# PATHOS_SOM_UART.net
KiCad netlist of a schematic drawn in Altium Designer
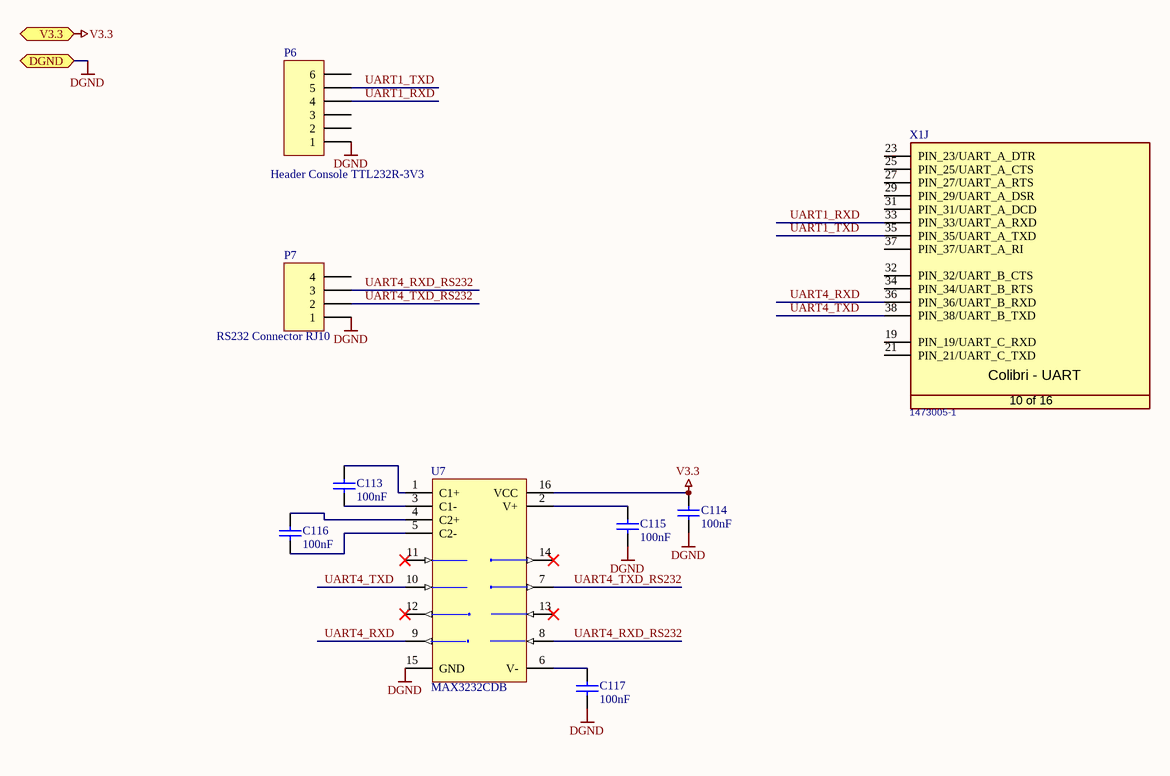
[diagram p0: PATHOS_SOM_UART.SchDoc]

(export (version "E")
  (design (tool "Eeschema 10.0.6"))
  (components
    (comp (ref "C113")
      (value "100nF")
      (footprint "0603_3D")
      (description "Capacitor")
      (fields (field (name "#PUBLISHER") "Dr. A. Heinzelmann"))
      (libsource (lib "EFS_Sensorboard") (part "C"))
    )
    (comp (ref "C114")
      (value "100nF")
      (footprint "0603_3D")
      (description "Capacitor")
      (fields (field (name "#PUBLISHER") "Dr. A. Heinzelmann"))
      (libsource (lib "EFS_Sensorboard") (part "C"))
    )
    (comp (ref "C115")
      (value "100nF")
      (footprint "0603_3D")
      (description "Capacitor")
      (fields (field (name "#PUBLISHER") "Dr. A. Heinzelmann"))
      (libsource (lib "EFS_Sensorboard") (part "C"))
    )
    (comp (ref "C116")
      (value "100nF")
      (footprint "0603_3D")
      (description "Capacitor")
      (fields (field (name "#PUBLISHER") "Dr. A. Heinzelmann"))
      (libsource (lib "EFS_Sensorboard") (part "C"))
    )
    (comp (ref "C117")
      (value "100nF")
      (footprint "0603_3D")
      (description "Capacitor")
      (fields (field (name "#PUBLISHER") "Dr. A. Heinzelmann"))
      (libsource (lib "EFS_Sensorboard") (part "C"))
    )
    (comp (ref "P6")
      (value "Header Console TTL232R-3V3")
      (footprint "Header - 1x6 - V")
      (description "Header, 6-Pin")
      (fields (field (name "PUBLISHER") "Altium Limited"))
      (libsource (lib "inf") (part "Header 1x6"))
    )
    (comp (ref "P7")
      (value "RS232 Connector RJ10")
      (footprint "95009-2447")
      (description "Header, 4-Pin")
      (fields (field (name "PUBLISHER") "Altium Limited"))
      (libsource (lib "Miscellaneous Connectors") (part "Header 4"))
    )
    (comp (ref "U7")
      (value "MAX3232CDB")
      (footprint "SSOP16_M_thinPins")
      (description "±15kV ESD-Protected, 3.0V to 5.5V, Low-Power, up to 250kbps, True RS-232 Transceiver")
      (fields (field (name "PUBLISHER") "Altium Limited"))
      (libsource (lib "Maxim Communication Transceiver") (part "MAX3232ECAE"))
    )
    (comp (ref "X1")
      (value "CON-Tyco-1473005-1-200-0.6mm")
      (footprint "T_Tyco_1473005-1")
      (description "SODIMM Connector")
      (fields (field (name "MANUFACTURER PART NO.") "1473005-1"))
      (libsource (lib "EFS_Sensorboard") (part "CON-Tyco-1473005-1-200-0.6mm"))
    )
  )
  (nets
    (net (code "1") (name "/UART1_RXD") (class "Default")
      (node (ref "P6") (pin "4") (pinfunction "4_4") (pintype "passive"))
      (node (ref "X1") (pin "33") (pinfunction "PIN_33/UART_A_RXD_33") (pintype "passive"))
    )
    (net (code "2") (name "/UART1_TXD") (class "Default")
      (node (ref "P6") (pin "5") (pinfunction "5_5") (pintype "passive"))
      (node (ref "X1") (pin "35") (pinfunction "PIN_35/UART_A_TXD_35") (pintype "passive"))
    )
    (net (code "3") (name "/UART4_RXD") (class "Default")
      (node (ref "U7") (pin "9") (pinfunction "R2OUT_9") (pintype "output"))
      (node (ref "X1") (pin "36") (pinfunction "PIN_36/UART_B_RXD_36") (pintype "passive"))
    )
    (net (code "4") (name "/UART4_RXD_RS232") (class "Default")
      (node (ref "P7") (pin "3") (pinfunction "3_3") (pintype "passive"))
      (node (ref "U7") (pin "8") (pinfunction "R2IN_8") (pintype "input"))
    )
    (net (code "5") (name "/UART4_TXD") (class "Default")
      (node (ref "U7") (pin "10") (pinfunction "T2IN_10") (pintype "input"))
      (node (ref "X1") (pin "38") (pinfunction "PIN_38/UART_B_TXD_38") (pintype "passive"))
    )
    (net (code "6") (name "/UART4_TXD_RS232") (class "Default")
      (node (ref "P7") (pin "2") (pinfunction "2_2") (pintype "passive"))
      (node (ref "U7") (pin "7") (pinfunction "T2OUT_7") (pintype "output"))
    )
    (net (code "7") (name "DGND") (class "Default")
      (node (ref "C114") (pin "1") (pinfunction "1_1") (pintype "passive"))
      (node (ref "C115") (pin "1") (pinfunction "1_1") (pintype "passive"))
      (node (ref "C117") (pin "1") (pinfunction "1_1") (pintype "passive"))
      (node (ref "P6") (pin "1") (pinfunction "1_1") (pintype "passive"))
      (node (ref "P7") (pin "1") (pinfunction "1_1") (pintype "passive"))
      (node (ref "U7") (pin "15") (pinfunction "GND_15") (pintype "passive"))
    )
    (net (code "8") (name "Net-(U7-C1+)") (class "Default")
      (node (ref "C113") (pin "2") (pinfunction "2_2") (pintype "passive"))
      (node (ref "U7") (pin "1") (pinfunction "C1+_1") (pintype "passive"))
    )
    (net (code "9") (name "Net-(U7-C1-)") (class "Default")
      (node (ref "C113") (pin "1") (pinfunction "1_1") (pintype "passive"))
      (node (ref "U7") (pin "3") (pinfunction "C1-_3") (pintype "passive"))
    )
    (net (code "10") (name "Net-(U7-C2+)") (class "Default")
      (node (ref "C116") (pin "2") (pinfunction "2_2") (pintype "passive"))
      (node (ref "U7") (pin "4") (pinfunction "C2+_4") (pintype "passive"))
    )
    (net (code "11") (name "Net-(U7-C2-)") (class "Default")
      (node (ref "C116") (pin "1") (pinfunction "1_1") (pintype "passive"))
      (node (ref "U7") (pin "5") (pinfunction "C2-_5") (pintype "passive"))
    )
    (net (code "12") (name "Net-(U7-V+)") (class "Default")
      (node (ref "C115") (pin "2") (pinfunction "2_2") (pintype "passive"))
      (node (ref "U7") (pin "2") (pinfunction "V+_2") (pintype "power_in"))
    )
    (net (code "13") (name "Net-(U7-V-)") (class "Default")
      (node (ref "C117") (pin "2") (pinfunction "2_2") (pintype "passive"))
      (node (ref "U7") (pin "6") (pinfunction "V-_6") (pintype "power_in"))
    )
    (net (code "14") (name "V3.3") (class "Default")
      (node (ref "C114") (pin "2") (pinfunction "2_2") (pintype "passive"))
      (node (ref "U7") (pin "16") (pinfunction "VCC_16") (pintype "passive"))
    )
    (net (code "15") (name "unconnected-(P6-Pad2)") (class "Default")
      (node (ref "P6") (pin "2") (pinfunction "2_2") (pintype "passive"))
    )
    (net (code "16") (name "unconnected-(P6-Pad3)") (class "Default")
      (node (ref "P6") (pin "3") (pinfunction "3_3") (pintype "passive"))
    )
    (net (code "17") (name "unconnected-(P6-Pad6)") (class "Default")
      (node (ref "P6") (pin "6") (pinfunction "6_6") (pintype "passive"))
    )
    (net (code "18") (name "unconnected-(P7-Pad4)") (class "Default")
      (node (ref "P7") (pin "4") (pinfunction "4_4") (pintype "passive"))
    )
    (net (code "19") (name "unconnected-(U7-R1IN-Pad13)") (class "Default")
      (node (ref "U7") (pin "13") (pinfunction "R1IN_13") (pintype "input+no_connect"))
    )
    (net (code "20") (name "unconnected-(U7-R1OUT-Pad12)") (class "Default")
      (node (ref "U7") (pin "12") (pinfunction "R1OUT_12") (pintype "output+no_connect"))
    )
    (net (code "21") (name "unconnected-(U7-T1IN-Pad11)") (class "Default")
      (node (ref "U7") (pin "11") (pinfunction "T1IN_11") (pintype "input+no_connect"))
    )
    (net (code "22") (name "unconnected-(U7-T1OUT-Pad14)") (class "Default")
      (node (ref "U7") (pin "14") (pinfunction "T1OUT_14") (pintype "output+no_connect"))
    )
    (net (code "23") (name "unconnected-(X1J-PIN_19{slash}UART_C_RXD-Pad19)") (class "Default")
      (node (ref "X1") (pin "19") (pinfunction "PIN_19/UART_C_RXD_19") (pintype "passive"))
    )
    (net (code "24") (name "unconnected-(X1J-PIN_21{slash}UART_C_TXD-Pad21)") (class "Default")
      (node (ref "X1") (pin "21") (pinfunction "PIN_21/UART_C_TXD_21") (pintype "passive"))
    )
    (net (code "25") (name "unconnected-(X1J-PIN_23{slash}UART_A_DTR-Pad23)") (class "Default")
      (node (ref "X1") (pin "23") (pinfunction "PIN_23/UART_A_DTR_23") (pintype "passive"))
    )
    (net (code "26") (name "unconnected-(X1J-PIN_25{slash}UART_A_CTS-Pad25)") (class "Default")
      (node (ref "X1") (pin "25") (pinfunction "PIN_25/UART_A_CTS_25") (pintype "passive"))
    )
    (net (code "27") (name "unconnected-(X1J-PIN_27{slash}UART_A_RTS-Pad27)") (class "Default")
      (node (ref "X1") (pin "27") (pinfunction "PIN_27/UART_A_RTS_27") (pintype "passive"))
    )
    (net (code "28") (name "unconnected-(X1J-PIN_29{slash}UART_A_DSR-Pad29)") (class "Default")
      (node (ref "X1") (pin "29") (pinfunction "PIN_29/UART_A_DSR_29") (pintype "passive"))
    )
    (net (code "29") (name "unconnected-(X1J-PIN_31{slash}UART_A_DCD-Pad31)") (class "Default")
      (node (ref "X1") (pin "31") (pinfunction "PIN_31/UART_A_DCD_31") (pintype "passive"))
    )
    (net (code "30") (name "unconnected-(X1J-PIN_32{slash}UART_B_CTS-Pad32)") (class "Default")
      (node (ref "X1") (pin "32") (pinfunction "PIN_32/UART_B_CTS_32") (pintype "passive"))
    )
    (net (code "31") (name "unconnected-(X1J-PIN_34{slash}UART_B_RTS-Pad34)") (class "Default")
      (node (ref "X1") (pin "34") (pinfunction "PIN_34/UART_B_RTS_34") (pintype "passive"))
    )
    (net (code "32") (name "unconnected-(X1J-PIN_37{slash}UART_A_RI-Pad37)") (class "Default")
      (node (ref "X1") (pin "37") (pinfunction "PIN_37/UART_A_RI_37") (pintype "passive"))
    )
  )
)
